# 2.net
KiCad netlist of a schematic drawn in Altium Designer
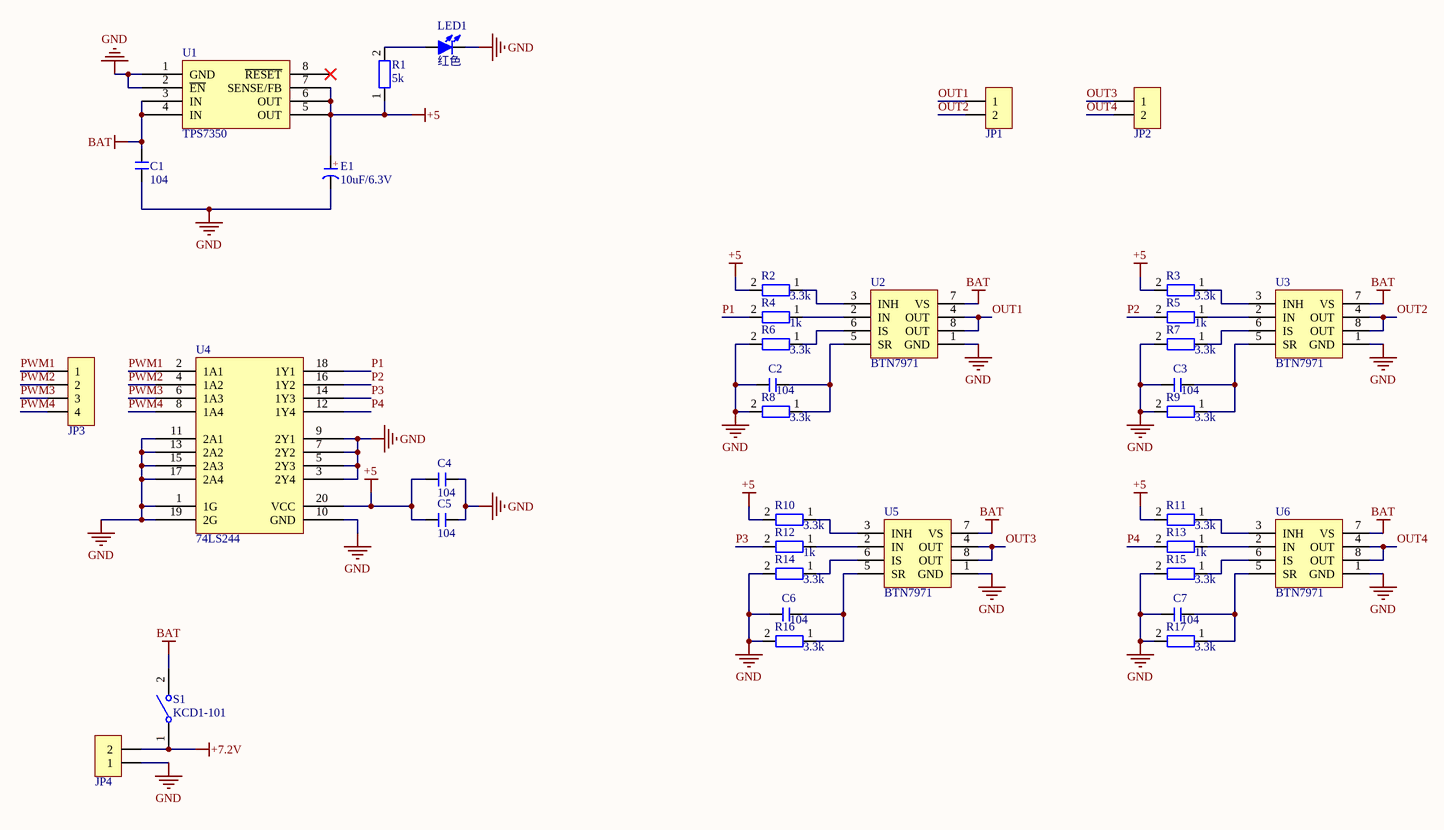
[diagram p0: 驱动2.SchDoc]

(export (version "E")
  (design (tool "Eeschema 10.0.6"))
  (components
    (comp (ref "C1")
      (value "104")
      (footprint "C 0805_M")
      (description "无极性贴片电容")
      (fields (field (name "版权归属") "源创客"))
      (libsource (lib "3.1   - 电阻-电容-电感") (part "C"))
    )
    (comp (ref "C2")
      (value "104")
      (footprint "C 0805_M")
      (description "无极性贴片电容")
      (fields (field (name "版权归属") "源创客"))
      (libsource (lib "3.1   - 电阻-电容-电感") (part "C"))
    )
    (comp (ref "C3")
      (value "104")
      (footprint "C 0805_M")
      (description "无极性贴片电容")
      (fields (field (name "版权归属") "源创客"))
      (libsource (lib "3.1   - 电阻-电容-电感") (part "C"))
    )
    (comp (ref "C4")
      (value "104")
      (footprint "C 0805_M")
      (description "无极性贴片电容")
      (fields (field (name "版权归属") "源创客"))
      (libsource (lib "3.1   - 电阻-电容-电感") (part "C"))
    )
    (comp (ref "C5")
      (value "104")
      (footprint "C 0805_M")
      (description "无极性贴片电容")
      (fields (field (name "版权归属") "源创客"))
      (libsource (lib "3.1   - 电阻-电容-电感") (part "C"))
    )
    (comp (ref "C6")
      (value "104")
      (footprint "C 0805_M")
      (description "无极性贴片电容")
      (fields (field (name "版权归属") "源创客"))
      (libsource (lib "3.1   - 电阻-电容-电感") (part "C"))
    )
    (comp (ref "C7")
      (value "104")
      (footprint "C 0805_M")
      (description "无极性贴片电容")
      (fields (field (name "版权归属") "源创客"))
      (libsource (lib "3.1   - 电阻-电容-电感") (part "C"))
    )
    (comp (ref "E1")
      (value "10uF/6.3V")
      (footprint "CD A(3216)")
      (description "贴片钽电容")
      (fields (field (name "版权归属") "源创客"))
      (libsource (lib "3.1   - 电阻-电容-电感") (part "C-CD"))
    )
    (comp (ref "JP1")
      (value "HDR-1X2")
      (footprint "KF128-5.08-2P")
      (description "2P接插件")
      (fields (field (name "版权归属") "源创客"))
      (libsource (lib "") (part "Header 2_1"))
    )
    (comp (ref "JP2")
      (value "HDR-1X2")
      (footprint "KF128-5.08-2P")
      (description "2P接插件")
      (fields (field (name "版权归属") "源创客"))
      (libsource (lib "") (part "Header 2_1"))
    )
    (comp (ref "JP3")
      (value "HDR-1X4")
      (footprint "XH2.54-LI-4P")
      (description "4P接插件")
      (fields (field (name "版权归属") "源创客"))
      (libsource (lib "4.5   - 接插件-脚距2.54") (part "Header 4"))
    )
    (comp (ref "JP4")
      (value "HDR-1X2")
      (footprint "KF128-5.08-2P")
      (description "2P接插件")
      (fields (field (name "版权归属") "源创客"))
      (libsource (lib "4.10 - 接插件-脚距5.08") (part "Header 2"))
    )
    (comp (ref "LED1")
      (value "红色")
      (footprint "LED 0805G")
      (description "贴片LED")
      (fields (field (name "版权归属") "源创客"))
      (libsource (lib "9.1   - LED") (part "LED-SMD"))
    )
    (comp (ref "R1")
      (value "5k")
      (footprint "R 0805_M")
      (description "贴片电阻")
      (fields (field (name "版权归属") "源创客"))
      (libsource (lib "3.1   - 电阻-电容-电感") (part "R"))
    )
    (comp (ref "R2")
      (value "3.3k")
      (footprint "R 0805_M")
      (description "贴片电阻")
      (fields (field (name "版权归属") "源创客"))
      (libsource (lib "3.1   - 电阻-电容-电感") (part "R"))
    )
    (comp (ref "R3")
      (value "3.3k")
      (footprint "R 0805_M")
      (description "贴片电阻")
      (fields (field (name "版权归属") "源创客"))
      (libsource (lib "3.1   - 电阻-电容-电感") (part "R"))
    )
    (comp (ref "R4")
      (value "1k")
      (footprint "R 0805_M")
      (description "贴片电阻")
      (fields (field (name "版权归属") "源创客"))
      (libsource (lib "3.1   - 电阻-电容-电感") (part "R"))
    )
    (comp (ref "R5")
      (value "1k")
      (footprint "R 0805_M")
      (description "贴片电阻")
      (fields (field (name "版权归属") "源创客"))
      (libsource (lib "3.1   - 电阻-电容-电感") (part "R"))
    )
    (comp (ref "R6")
      (value "3.3k")
      (footprint "R 0805_M")
      (description "贴片电阻")
      (fields (field (name "版权归属") "源创客"))
      (libsource (lib "3.1   - 电阻-电容-电感") (part "R"))
    )
    (comp (ref "R7")
      (value "3.3k")
      (footprint "R 0805_M")
      (description "贴片电阻")
      (fields (field (name "版权归属") "源创客"))
      (libsource (lib "3.1   - 电阻-电容-电感") (part "R"))
    )
    (comp (ref "R8")
      (value "3.3k")
      (footprint "R 0805_M")
      (description "贴片电阻")
      (fields (field (name "版权归属") "源创客"))
      (libsource (lib "3.1   - 电阻-电容-电感") (part "R"))
    )
    (comp (ref "R9")
      (value "3.3k")
      (footprint "R 0805_M")
      (description "贴片电阻")
      (fields (field (name "版权归属") "源创客"))
      (libsource (lib "3.1   - 电阻-电容-电感") (part "R"))
    )
    (comp (ref "R10")
      (value "3.3k")
      (footprint "R 0805_M")
      (description "贴片电阻")
      (fields (field (name "版权归属") "源创客"))
      (libsource (lib "3.1   - 电阻-电容-电感") (part "R"))
    )
    (comp (ref "R11")
      (value "3.3k")
      (footprint "R 0805_M")
      (description "贴片电阻")
      (fields (field (name "版权归属") "源创客"))
      (libsource (lib "3.1   - 电阻-电容-电感") (part "R"))
    )
    (comp (ref "R12")
      (value "1k")
      (footprint "R 0805_M")
      (description "贴片电阻")
      (fields (field (name "版权归属") "源创客"))
      (libsource (lib "3.1   - 电阻-电容-电感") (part "R"))
    )
    (comp (ref "R13")
      (value "1k")
      (footprint "R 0805_M")
      (description "贴片电阻")
      (fields (field (name "版权归属") "源创客"))
      (libsource (lib "3.1   - 电阻-电容-电感") (part "R"))
    )
    (comp (ref "R14")
      (value "3.3k")
      (footprint "R 0805_M")
      (description "贴片电阻")
      (fields (field (name "版权归属") "源创客"))
      (libsource (lib "3.1   - 电阻-电容-电感") (part "R"))
    )
    (comp (ref "R15")
      (value "3.3k")
      (footprint "R 0805_M")
      (description "贴片电阻")
      (fields (field (name "版权归属") "源创客"))
      (libsource (lib "3.1   - 电阻-电容-电感") (part "R"))
    )
    (comp (ref "R16")
      (value "3.3k")
      (footprint "R 0805_M")
      (description "贴片电阻")
      (fields (field (name "版权归属") "源创客"))
      (libsource (lib "3.1   - 电阻-电容-电感") (part "R"))
    )
    (comp (ref "R17")
      (value "3.3k")
      (footprint "R 0805_M")
      (description "贴片电阻")
      (fields (field (name "版权归属") "源创客"))
      (libsource (lib "3.1   - 电阻-电容-电感") (part "R"))
    )
    (comp (ref "S1")
      (value "KCD1-101")
      (footprint "KCD1-101")
      (description "1路单刀船型开关")
      (fields (field (name "版权归属") "源创客"))
      (libsource (lib "5.1   - 按键-开关") (part "KCD1-101"))
    )
    (comp (ref "U1")
      (value "TPS7350")
      (footprint "SOP8")
      (description "稳压")
      (libsource (lib "tps7350") (part "TPS7350"))
    )
    (comp (ref "U2")
      (value "BTN7971")
      (footprint "DPAK127P1615X127-8N")
      (libsource (lib "驱动2") (part "BTN7971"))
    )
    (comp (ref "U3")
      (value "BTN7971")
      (footprint "DPAK127P1615X127-8N")
      (libsource (lib "驱动2") (part "BTN7971"))
    )
    (comp (ref "U4") (value "74LS244") (footprint "SOP20") (libsource (lib "驱动2") (part "74LS244")))
    (comp (ref "U5")
      (value "BTN7971")
      (footprint "DPAK127P1615X127-8N")
      (libsource (lib "驱动2") (part "BTN7971"))
    )
    (comp (ref "U6")
      (value "BTN7971")
      (footprint "DPAK127P1615X127-8N")
      (libsource (lib "驱动2") (part "BTN7971"))
    )
  )
  (nets
    (net (code "1") (name "+5") (class "Default")
      (node (ref "C4") (pin "1") (pinfunction "1_1") (pintype "passive"))
      (node (ref "C5") (pin "1") (pinfunction "1_1") (pintype "passive"))
      (node (ref "E1") (pin "1") (pinfunction "A_1") (pintype "passive"))
      (node (ref "R1") (pin "1") (pinfunction "1_1") (pintype "passive"))
      (node (ref "R10") (pin "2") (pinfunction "2_2") (pintype "passive"))
      (node (ref "R11") (pin "2") (pinfunction "2_2") (pintype "passive"))
      (node (ref "R2") (pin "2") (pinfunction "2_2") (pintype "passive"))
      (node (ref "R3") (pin "2") (pinfunction "2_2") (pintype "passive"))
      (node (ref "U1") (pin "5") (pinfunction "OUT_5") (pintype "passive"))
      (node (ref "U1") (pin "6") (pinfunction "OUT_6") (pintype "passive"))
      (node (ref "U1") (pin "7") (pinfunction "SENSE/FB_7") (pintype "passive"))
      (node (ref "U4") (pin "20") (pinfunction "VCC_20") (pintype "passive"))
    )
    (net (code "2") (name "+7.2V") (class "Default")
      (node (ref "JP4") (pin "2") (pinfunction "2_2") (pintype "passive"))
      (node (ref "S1") (pin "1") (pinfunction "1_1") (pintype "passive"))
    )
    (net (code "3") (name "/OUT1") (class "Default")
      (node (ref "JP1") (pin "1") (pinfunction "1_1") (pintype "passive"))
      (node (ref "U2") (pin "4") (pinfunction "OUT_4") (pintype "passive"))
      (node (ref "U2") (pin "8") (pinfunction "OUT_8") (pintype "passive"))
    )
    (net (code "4") (name "/OUT2") (class "Default")
      (node (ref "JP1") (pin "2") (pinfunction "2_2") (pintype "passive"))
      (node (ref "U3") (pin "4") (pinfunction "OUT_4") (pintype "passive"))
      (node (ref "U3") (pin "8") (pinfunction "OUT_8") (pintype "passive"))
    )
    (net (code "5") (name "/OUT3") (class "Default")
      (node (ref "JP2") (pin "1") (pinfunction "1_1") (pintype "passive"))
      (node (ref "U5") (pin "4") (pinfunction "OUT_4") (pintype "passive"))
      (node (ref "U5") (pin "8") (pinfunction "OUT_8") (pintype "passive"))
    )
    (net (code "6") (name "/OUT4") (class "Default")
      (node (ref "JP2") (pin "2") (pinfunction "2_2") (pintype "passive"))
      (node (ref "U6") (pin "4") (pinfunction "OUT_4") (pintype "passive"))
      (node (ref "U6") (pin "8") (pinfunction "OUT_8") (pintype "passive"))
    )
    (net (code "7") (name "/P1") (class "Default")
      (node (ref "R4") (pin "2") (pinfunction "2_2") (pintype "passive"))
      (node (ref "U4") (pin "18") (pinfunction "1Y1_18") (pintype "passive"))
    )
    (net (code "8") (name "/P2") (class "Default")
      (node (ref "R5") (pin "2") (pinfunction "2_2") (pintype "passive"))
      (node (ref "U4") (pin "16") (pinfunction "1Y2_16") (pintype "passive"))
    )
    (net (code "9") (name "/P3") (class "Default")
      (node (ref "R12") (pin "2") (pinfunction "2_2") (pintype "passive"))
      (node (ref "U4") (pin "14") (pinfunction "1Y3_14") (pintype "passive"))
    )
    (net (code "10") (name "/P4") (class "Default")
      (node (ref "R13") (pin "2") (pinfunction "2_2") (pintype "passive"))
      (node (ref "U4") (pin "12") (pinfunction "1Y4_12") (pintype "passive"))
    )
    (net (code "11") (name "/PWM1") (class "Default")
      (node (ref "JP3") (pin "1") (pinfunction "1_1") (pintype "passive"))
      (node (ref "U4") (pin "2") (pinfunction "1A1_2") (pintype "passive"))
    )
    (net (code "12") (name "/PWM2") (class "Default")
      (node (ref "JP3") (pin "2") (pinfunction "2_2") (pintype "passive"))
      (node (ref "U4") (pin "4") (pinfunction "1A2_4") (pintype "passive"))
    )
    (net (code "13") (name "/PWM3") (class "Default")
      (node (ref "JP3") (pin "3") (pinfunction "3_3") (pintype "passive"))
      (node (ref "U4") (pin "6") (pinfunction "1A3_6") (pintype "passive"))
    )
    (net (code "14") (name "/PWM4") (class "Default")
      (node (ref "JP3") (pin "4") (pinfunction "4_4") (pintype "passive"))
      (node (ref "U4") (pin "8") (pinfunction "1A4_8") (pintype "passive"))
    )
    (net (code "15") (name "BAT") (class "Default")
      (node (ref "C1") (pin "2") (pinfunction "2_2") (pintype "passive"))
      (node (ref "S1") (pin "2") (pinfunction "2_2") (pintype "passive"))
      (node (ref "U1") (pin "3") (pinfunction "IN_3") (pintype "passive"))
      (node (ref "U1") (pin "4") (pinfunction "IN_4") (pintype "passive"))
      (node (ref "U2") (pin "7") (pinfunction "VS_7") (pintype "passive"))
      (node (ref "U3") (pin "7") (pinfunction "VS_7") (pintype "passive"))
      (node (ref "U5") (pin "7") (pinfunction "VS_7") (pintype "passive"))
      (node (ref "U6") (pin "7") (pinfunction "VS_7") (pintype "passive"))
    )
    (net (code "16") (name "GND") (class "Default")
      (node (ref "C1") (pin "1") (pinfunction "1_1") (pintype "passive"))
      (node (ref "C2") (pin "2") (pinfunction "2_2") (pintype "passive"))
      (node (ref "C3") (pin "2") (pinfunction "2_2") (pintype "passive"))
      (node (ref "C4") (pin "2") (pinfunction "2_2") (pintype "passive"))
      (node (ref "C5") (pin "2") (pinfunction "2_2") (pintype "passive"))
      (node (ref "C6") (pin "2") (pinfunction "2_2") (pintype "passive"))
      (node (ref "C7") (pin "2") (pinfunction "2_2") (pintype "passive"))
      (node (ref "E1") (pin "2") (pinfunction "K_2") (pintype "passive"))
      (node (ref "JP4") (pin "1") (pinfunction "1_1") (pintype "passive"))
      (node (ref "LED1") (pin "2") (pinfunction "K_2") (pintype "passive"))
      (node (ref "R14") (pin "2") (pinfunction "2_2") (pintype "passive"))
      (node (ref "R15") (pin "2") (pinfunction "2_2") (pintype "passive"))
      (node (ref "R16") (pin "2") (pinfunction "2_2") (pintype "passive"))
      (node (ref "R17") (pin "2") (pinfunction "2_2") (pintype "passive"))
      (node (ref "R6") (pin "2") (pinfunction "2_2") (pintype "passive"))
      (node (ref "R7") (pin "2") (pinfunction "2_2") (pintype "passive"))
      (node (ref "R8") (pin "2") (pinfunction "2_2") (pintype "passive"))
      (node (ref "R9") (pin "2") (pinfunction "2_2") (pintype "passive"))
      (node (ref "U1") (pin "1") (pinfunction "GND_1") (pintype "passive"))
      (node (ref "U1") (pin "2") (pinfunction "~{EN}_2") (pintype "passive"))
      (node (ref "U2") (pin "1") (pinfunction "GND_1") (pintype "passive"))
      (node (ref "U3") (pin "1") (pinfunction "GND_1") (pintype "passive"))
      (node (ref "U4") (pin "1") (pinfunction "1G_1") (pintype "passive"))
      (node (ref "U4") (pin "10") (pinfunction "GND_10") (pintype "passive"))
      (node (ref "U4") (pin "11") (pinfunction "2A1_11") (pintype "passive"))
      (node (ref "U4") (pin "13") (pinfunction "2A2_13") (pintype "passive"))
      (node (ref "U4") (pin "15") (pinfunction "2A3_15") (pintype "passive"))
      (node (ref "U4") (pin "17") (pinfunction "2A4_17") (pintype "passive"))
      (node (ref "U4") (pin "19") (pinfunction "2G_19") (pintype "passive"))
      (node (ref "U4") (pin "3") (pinfunction "2Y4_3") (pintype "passive"))
      (node (ref "U4") (pin "5") (pinfunction "2Y3_5") (pintype "passive"))
      (node (ref "U4") (pin "7") (pinfunction "2Y2_7") (pintype "passive"))
      (node (ref "U4") (pin "9") (pinfunction "2Y1_9") (pintype "passive"))
      (node (ref "U5") (pin "1") (pinfunction "GND_1") (pintype "passive"))
      (node (ref "U6") (pin "1") (pinfunction "GND_1") (pintype "passive"))
    )
    (net (code "17") (name "Net-(LED1-A)") (class "Default")
      (node (ref "LED1") (pin "1") (pinfunction "A_1") (pintype "passive"))
      (node (ref "R1") (pin "2") (pinfunction "2_2") (pintype "passive"))
    )
    (net (code "18") (name "Net-(U2-IN)") (class "Default")
      (node (ref "R4") (pin "1") (pinfunction "1_1") (pintype "passive"))
      (node (ref "U2") (pin "2") (pinfunction "IN_2") (pintype "passive"))
    )
    (net (code "19") (name "Net-(U2-INH)") (class "Default")
      (node (ref "R2") (pin "1") (pinfunction "1_1") (pintype "passive"))
      (node (ref "U2") (pin "3") (pinfunction "INH_3") (pintype "passive"))
    )
    (net (code "20") (name "Net-(U2-IS)") (class "Default")
      (node (ref "R6") (pin "1") (pinfunction "1_1") (pintype "passive"))
      (node (ref "U2") (pin "6") (pinfunction "IS_6") (pintype "passive"))
    )
    (net (code "21") (name "Net-(U2-SR)") (class "Default")
      (node (ref "C2") (pin "1") (pinfunction "1_1") (pintype "passive"))
      (node (ref "R8") (pin "1") (pinfunction "1_1") (pintype "passive"))
      (node (ref "U2") (pin "5") (pinfunction "SR_5") (pintype "passive"))
    )
    (net (code "22") (name "Net-(U3-IN)") (class "Default")
      (node (ref "R5") (pin "1") (pinfunction "1_1") (pintype "passive"))
      (node (ref "U3") (pin "2") (pinfunction "IN_2") (pintype "passive"))
    )
    (net (code "23") (name "Net-(U3-INH)") (class "Default")
      (node (ref "R3") (pin "1") (pinfunction "1_1") (pintype "passive"))
      (node (ref "U3") (pin "3") (pinfunction "INH_3") (pintype "passive"))
    )
    (net (code "24") (name "Net-(U3-IS)") (class "Default")
      (node (ref "R7") (pin "1") (pinfunction "1_1") (pintype "passive"))
      (node (ref "U3") (pin "6") (pinfunction "IS_6") (pintype "passive"))
    )
    (net (code "25") (name "Net-(U3-SR)") (class "Default")
      (node (ref "C3") (pin "1") (pinfunction "1_1") (pintype "passive"))
      (node (ref "R9") (pin "1") (pinfunction "1_1") (pintype "passive"))
      (node (ref "U3") (pin "5") (pinfunction "SR_5") (pintype "passive"))
    )
    (net (code "26") (name "Net-(U5-IN)") (class "Default")
      (node (ref "R12") (pin "1") (pinfunction "1_1") (pintype "passive"))
      (node (ref "U5") (pin "2") (pinfunction "IN_2") (pintype "passive"))
    )
    (net (code "27") (name "Net-(U5-INH)") (class "Default")
      (node (ref "R10") (pin "1") (pinfunction "1_1") (pintype "passive"))
      (node (ref "U5") (pin "3") (pinfunction "INH_3") (pintype "passive"))
    )
    (net (code "28") (name "Net-(U5-IS)") (class "Default")
      (node (ref "R14") (pin "1") (pinfunction "1_1") (pintype "passive"))
      (node (ref "U5") (pin "6") (pinfunction "IS_6") (pintype "passive"))
    )
    (net (code "29") (name "Net-(U5-SR)") (class "Default")
      (node (ref "C6") (pin "1") (pinfunction "1_1") (pintype "passive"))
      (node (ref "R16") (pin "1") (pinfunction "1_1") (pintype "passive"))
      (node (ref "U5") (pin "5") (pinfunction "SR_5") (pintype "passive"))
    )
    (net (code "30") (name "Net-(U6-IN)") (class "Default")
      (node (ref "R13") (pin "1") (pinfunction "1_1") (pintype "passive"))
      (node (ref "U6") (pin "2") (pinfunction "IN_2") (pintype "passive"))
    )
    (net (code "31") (name "Net-(U6-INH)") (class "Default")
      (node (ref "R11") (pin "1") (pinfunction "1_1") (pintype "passive"))
      (node (ref "U6") (pin "3") (pinfunction "INH_3") (pintype "passive"))
    )
    (net (code "32") (name "Net-(U6-IS)") (class "Default")
      (node (ref "R15") (pin "1") (pinfunction "1_1") (pintype "passive"))
      (node (ref "U6") (pin "6") (pinfunction "IS_6") (pintype "passive"))
    )
    (net (code "33") (name "Net-(U6-SR)") (class "Default")
      (node (ref "C7") (pin "1") (pinfunction "1_1") (pintype "passive"))
      (node (ref "R17") (pin "1") (pinfunction "1_1") (pintype "passive"))
      (node (ref "U6") (pin "5") (pinfunction "SR_5") (pintype "passive"))
    )
    (net (code "34") (name "unconnected-(U1-~{RESET}-Pad8)") (class "Default")
      (node (ref "U1") (pin "8") (pinfunction "~{RESET}_8") (pintype "passive+no_connect"))
    )
  )
)
